# Moter_driver.net
KiCad netlist of a schematic drawn in Altium Designer
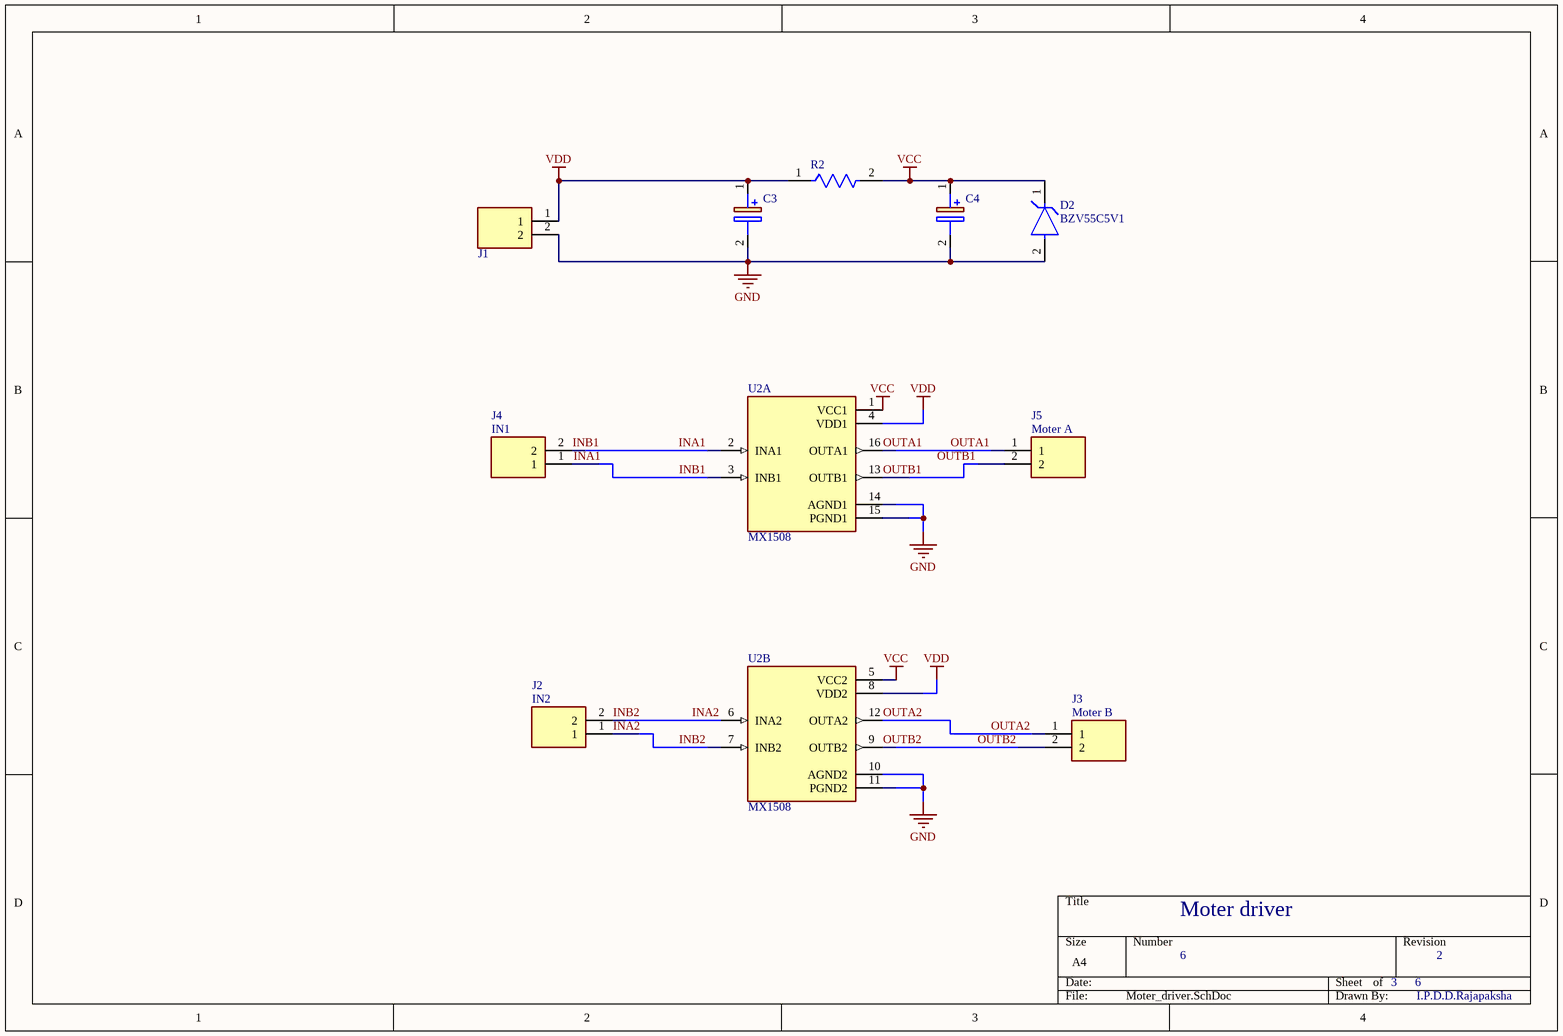
[diagram p0: Moter_driver.SchDoc]

(export (version "E")
  (design (tool "Eeschema 10.0.6"))
  (components
    (comp (ref "C3")
      (value "EEV107M016S9GAA")
      (footprint "SamacSys:CAPAE660X565N")
      (description "Capacitor Polarised")
      (fields (field (name "MOUSER PART NUMBER") "80-EEV107M016S9GAA"))
      (libsource (lib "*") (part "EEV107M016S9GAA"))
    )
    (comp (ref "C4")
      (value "EEV107M016S9GAA")
      (footprint "SamacSys:CAPAE660X565N")
      (description "Capacitor Polarised")
      (fields (field (name "MOUSER PART NUMBER") "80-EEV107M016S9GAA"))
      (libsource (lib "*") (part "EEV107M016S9GAA"))
    )
    (comp (ref "D2")
      (value "BZV55C5V1")
      (footprint "FP-DO-213AA-MFG")
      (description "BZV55C5V1 Diode Zener Single 5.1V 5% 2-Pin DO-213AA Bag")
      (fields (field (name "TOLERANCE") "6%"))
      (libsource (lib "Altium Content Vault") (part "f813f71cba58e380607f5dd3caf9714"))
    )
    (comp (ref "J1")
      (value "M20-9990246")
      (footprint "SamacSys:HDRV2W66P0X254_1X2_508X254X874P")
      (description "Connector")
      (fields (field (name "MOUSER PART NUMBER") "855-M20-9990246"))
      (libsource (lib "") (part "M20-9990246_1"))
    )
    (comp (ref "J2")
      (value "M20-9990246")
      (footprint "SamacSys:HDRV2W66P0X254_1X2_508X254X874P")
      (description "Connector")
      (fields (field (name "MOUSER PART NUMBER") "855-M20-9990246") (field (name "NAME") "IN2"))
      (libsource (lib "*") (part "M20-9990246"))
    )
    (comp (ref "J3")
      (value "M20-9990246")
      (footprint "SamacSys:HDRV2W66P0X254_1X2_508X254X874P")
      (description "Connector")
      (fields (field (name "MOUSER PART NUMBER") "855-M20-9990246") (field (name "PARAMETER 1") "Moter B"))
      (libsource (lib "") (part "M20-9990246_2"))
    )
    (comp (ref "J4")
      (value "M20-9990246")
      (footprint "SamacSys:HDRV2W66P0X254_1X2_508X254X874P")
      (description "Connector")
      (fields (field (name "MOUSER PART NUMBER") "855-M20-9990246") (field (name "NAME") "IN1"))
      (libsource (lib "*") (part "M20-9990246"))
    )
    (comp (ref "J5")
      (value "M20-9990246")
      (footprint "SamacSys:HDRV2W66P0X254_1X2_508X254X874P")
      (description "Connector")
      (fields (field (name "MOUSER PART NUMBER") "855-M20-9990246") (field (name "PARAMETER 1") "Moter A"))
      (libsource (lib "") (part "M20-9990246_2"))
    )
    (comp (ref "R2")
      (value "ESR03EZPJ221")
      (footprint "FP-ESR03-MFG")
      (description "220Ω ±5% 0.25W 0603 Anti-Surge Chip Resistor AEC-Q200")
      (fields (field (name "TOLERANCE") "5%"))
      (libsource (lib "Altium Content Vault") (part "1029c3af85768c4190bb7ad29bc67b5"))
    )
    (comp (ref "U2")
      (value "MX1508")
      (footprint "SOIC127P600X177-16N")
      (fields (field (name "MF") "Sinotech Mixic Electronics Co., Ltd"))
      (libsource (lib "MX1508") (part "MX1508"))
    )
  )
  (nets
    (net (code "1") (name "/INA1") (class "Default")
      (node (ref "J4") (pin "1") (pinfunction "1_1") (pintype "passive"))
      (node (ref "J4") (pin "2") (pinfunction "2_2") (pintype "passive"))
      (node (ref "U2") (pin "2") (pinfunction "INA1_2") (pintype "input"))
      (node (ref "U2") (pin "3") (pinfunction "INB1_3") (pintype "input"))
    )
    (net (code "2") (name "/INA2") (class "Default")
      (node (ref "J2") (pin "1") (pinfunction "1_1") (pintype "passive"))
      (node (ref "J2") (pin "2") (pinfunction "2_2") (pintype "passive"))
      (node (ref "U2") (pin "6") (pinfunction "INA2_6") (pintype "input"))
      (node (ref "U2") (pin "7") (pinfunction "INB2_7") (pintype "input"))
    )
    (net (code "3") (name "/OUTA1") (class "Default")
      (node (ref "J5") (pin "1") (pinfunction "1_1") (pintype "passive"))
      (node (ref "U2") (pin "16") (pinfunction "OUTA1_16") (pintype "output"))
    )
    (net (code "4") (name "/OUTA2") (class "Default")
      (node (ref "J3") (pin "1") (pinfunction "1_1") (pintype "passive"))
      (node (ref "U2") (pin "12") (pinfunction "OUTA2_12") (pintype "output"))
    )
    (net (code "5") (name "/OUTB1") (class "Default")
      (node (ref "J5") (pin "2") (pinfunction "2_2") (pintype "passive"))
      (node (ref "U2") (pin "13") (pinfunction "OUTB1_13") (pintype "output"))
    )
    (net (code "6") (name "/OUTB2") (class "Default")
      (node (ref "J3") (pin "2") (pinfunction "2_2") (pintype "passive"))
      (node (ref "U2") (pin "9") (pinfunction "OUTB2_9") (pintype "output"))
    )
    (net (code "7") (name "GND") (class "Default")
      (node (ref "C3") (pin "2") (pinfunction "-_2") (pintype "passive"))
      (node (ref "C4") (pin "2") (pinfunction "-_2") (pintype "passive"))
      (node (ref "D2") (pin "2") (pinfunction "A_2") (pintype "passive"))
      (node (ref "J1") (pin "2") (pinfunction "2_2") (pintype "passive"))
      (node (ref "U2") (pin "10") (pinfunction "AGND2_10") (pintype "power_in"))
      (node (ref "U2") (pin "11") (pinfunction "PGND2_11") (pintype "power_in"))
      (node (ref "U2") (pin "14") (pinfunction "AGND1_14") (pintype "power_in"))
      (node (ref "U2") (pin "15") (pinfunction "PGND1_15") (pintype "power_in"))
    )
    (net (code "8") (name "VCC") (class "Default")
      (node (ref "C4") (pin "1") (pinfunction "+_1") (pintype "passive"))
      (node (ref "D2") (pin "1") (pinfunction "C_1") (pintype "passive"))
      (node (ref "R2") (pin "2") (pinfunction "2_2") (pintype "passive"))
      (node (ref "U2") (pin "1") (pinfunction "VCC1_1") (pintype "power_in"))
      (node (ref "U2") (pin "5") (pinfunction "VCC2_5") (pintype "power_in"))
    )
    (net (code "9") (name "VDD") (class "Default")
      (node (ref "C3") (pin "1") (pinfunction "+_1") (pintype "passive"))
      (node (ref "J1") (pin "1") (pinfunction "1_1") (pintype "passive"))
      (node (ref "R2") (pin "1") (pinfunction "1_1") (pintype "passive"))
      (node (ref "U2") (pin "4") (pinfunction "VDD1_4") (pintype "power_in"))
      (node (ref "U2") (pin "8") (pinfunction "VDD2_8") (pintype "power_in"))
    )
  )
)
